# flyback.net
KiCad netlist of a schematic drawn in Altium Designer
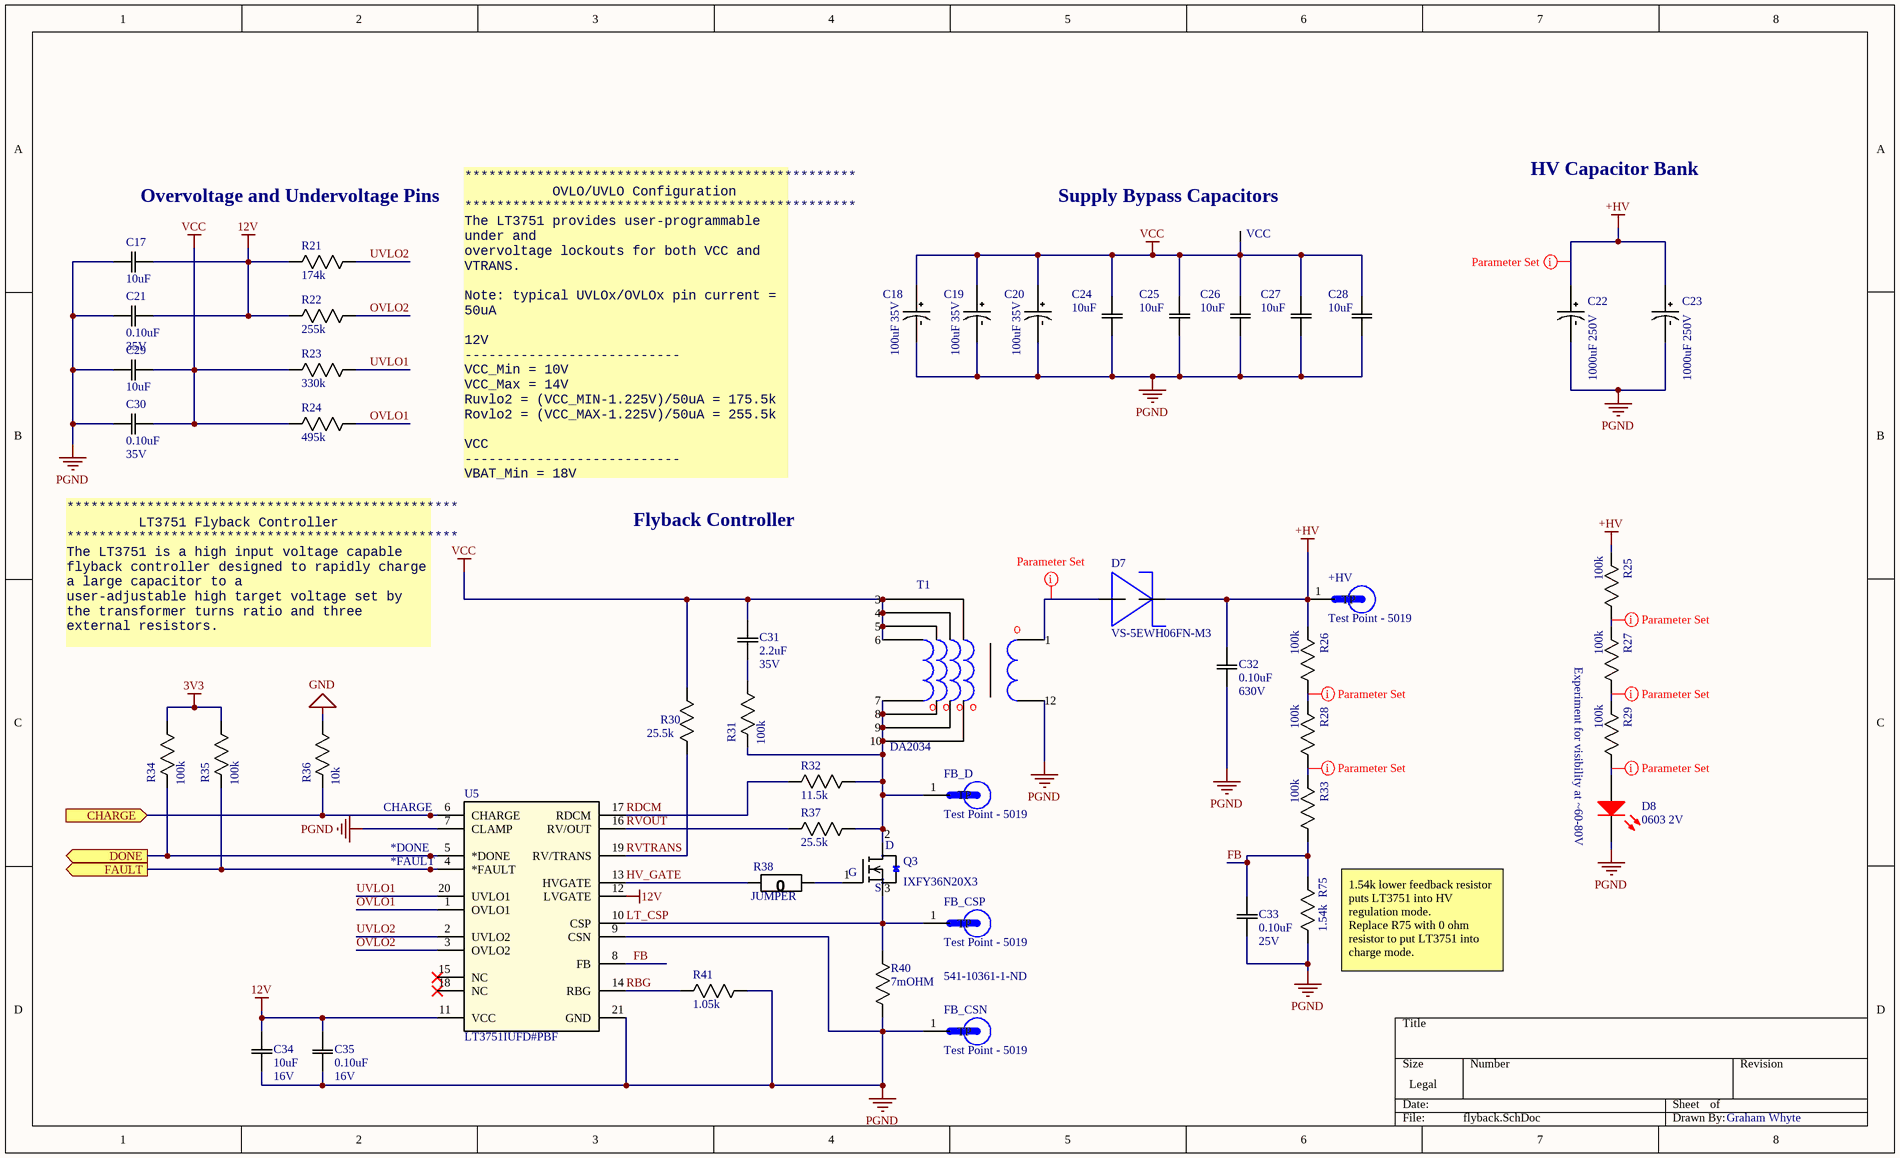
[diagram p0: flyback.SchDoc]

(export (version "E")
  (design (tool "Eeschema 10.0.6"))
  (components
    (comp (ref "*DONE")
      (value "Test Point (Via)")
      (footprint "TP")
      (libsource (lib "IC_Library") (part "Test Point (Via)"))
    )
    (comp (ref "*FAULT")
      (value "Test Point (Via)")
      (footprint "TP")
      (libsource (lib "IC_Library") (part "Test Point (Via)"))
    )
    (comp (ref "+HV")
      (value "Test Point - 5019")
      (footprint "TP380X203")
      (description "PC Test Point, Miniature Phosphor Bronze, Silver Plating Surface Mount Mounting Type")
      (fields (field (name "MP") "5019") (field (name "MF") "Keystone Electronics"))
      (libsource (lib "IC_Library") (part "Test Point - 5019"))
    )
    (comp (ref "C17")
      (value "10uF")
      (footprint "0805")
      (description "CAP CER 10UF 35V X7R 0805")
      (fields (field (name "TOLERANCE") "10%") (field (name "PART NUMBER") "CAP 10uF 35V"))
      (libsource (lib "capacitor_library") (part "CAP 10uF 35V"))
    )
    (comp (ref "C18")
      (value "100uF 35V")
      (footprint "CAP POL ALU 6.3x5.8")
      (description "CAP ALUM 100UF 35V SMD")
      (fields (field (name "TOLERANCE") "20%") (field (name "PART NUMBER") "CAP POL 100uF SMD"))
      (libsource (lib "capacitor_library") (part "CAP POL 100uF SMD"))
    )
    (comp (ref "C19")
      (value "100uF 35V")
      (footprint "CAP POL ALU 6.3x5.8")
      (description "CAP ALUM 100UF 35V SMD")
      (fields (field (name "TOLERANCE") "20%") (field (name "PART NUMBER") "CAP POL 100uF SMD"))
      (libsource (lib "capacitor_library") (part "CAP POL 100uF SMD"))
    )
    (comp (ref "C20")
      (value "100uF 35V")
      (footprint "CAP POL ALU 6.3x5.8")
      (description "CAP ALUM 100UF 35V SMD")
      (fields (field (name "TOLERANCE") "20%") (field (name "PART NUMBER") "CAP POL 100uF SMD"))
      (libsource (lib "capacitor_library") (part "CAP POL 100uF SMD"))
    )
    (comp (ref "C21")
      (value "0.10uF")
      (footprint "0805")
      (description "CAP CER 0.10UF 35V X7R 0805")
      (fields
        (field (name "TOLERANCE") "10%")
        (field (name "RATING") "35V")
        (field (name "PART NUMBER") "CAP 0.10uF 35V")
      )
      (libsource (lib "capacitor_library") (part "CAP 0.10uF 35V"))
    )
    (comp (ref "C22")
      (value "1000uF 250V")
      (footprint "RADIAL, CAN - THRU 25.4mm")
      (description "United Chemi-Con\r\nESMQ251VSN102MQ45S")
      (fields
        (field (name "MANUFACTURER") "United Chemi-Con")
        (field (name "MANUFACTURER PART NUMBER") "ESMQ251VSN102MQ45S")
      )
      (libsource (lib "capacitor_library") (part "CAP POL 1000uF"))
    )
    (comp (ref "C23")
      (value "1000uF 250V")
      (footprint "RADIAL, CAN - THRU 25.4mm")
      (description "United Chemi-Con\r\nESMQ251VSN102MQ45S")
      (fields
        (field (name "MANUFACTURER") "United Chemi-Con")
        (field (name "MANUFACTURER PART NUMBER") "ESMQ251VSN102MQ45S")
      )
      (libsource (lib "capacitor_library") (part "CAP POL 1000uF"))
    )
    (comp (ref "C24")
      (value "10uF")
      (footprint "0805")
      (description "CAP CER 10UF 35V X7R 0805")
      (fields (field (name "TOLERANCE") "10%") (field (name "PART NUMBER") "CAP 10uF 35V"))
      (libsource (lib "capacitor_library") (part "CAP 10uF 35V"))
    )
    (comp (ref "C25")
      (value "10uF")
      (footprint "0805")
      (description "CAP CER 10UF 35V X7R 0805")
      (fields (field (name "TOLERANCE") "10%") (field (name "PART NUMBER") "CAP 10uF 35V"))
      (libsource (lib "capacitor_library") (part "CAP 10uF 35V"))
    )
    (comp (ref "C26")
      (value "10uF")
      (footprint "0805")
      (description "CAP CER 10UF 35V X7R 0805")
      (fields (field (name "TOLERANCE") "10%") (field (name "PART NUMBER") "CAP 10uF 35V"))
      (libsource (lib "capacitor_library") (part "CAP 10uF 35V"))
    )
    (comp (ref "C27")
      (value "10uF")
      (footprint "0805")
      (description "CAP CER 10UF 35V X7R 0805")
      (fields (field (name "TOLERANCE") "10%") (field (name "PART NUMBER") "CAP 10uF 35V"))
      (libsource (lib "capacitor_library") (part "CAP 10uF 35V"))
    )
    (comp (ref "C28")
      (value "10uF")
      (footprint "0805")
      (description "CAP CER 10UF 35V X7R 0805")
      (fields (field (name "TOLERANCE") "10%") (field (name "PART NUMBER") "CAP 10uF 35V"))
      (libsource (lib "capacitor_library") (part "CAP 10uF 35V"))
    )
    (comp (ref "C29")
      (value "10uF")
      (footprint "0805")
      (description "CAP CER 10UF 35V X7R 0805")
      (fields (field (name "TOLERANCE") "10%") (field (name "PART NUMBER") "CAP 10uF 35V"))
      (libsource (lib "capacitor_library") (part "CAP 10uF 35V"))
    )
    (comp (ref "C30")
      (value "0.10uF")
      (footprint "0805")
      (description "CAP CER 0.10UF 35V X7R 0805")
      (fields
        (field (name "TOLERANCE") "10%")
        (field (name "RATING") "35V")
        (field (name "PART NUMBER") "CAP 0.10uF 35V")
      )
      (libsource (lib "capacitor_library") (part "CAP 0.10uF 35V"))
    )
    (comp (ref "C31")
      (value "2.2uF")
      (footprint "0603")
      (description "CAP CER 2.2UF 35V X7R 0603/0805")
      (fields
        (field (name "TOLERANCE") "10%")
        (field (name "RATING") "35V")
        (field (name "PART NUMBER") "CAP 2.2uF 35V")
      )
      (libsource (lib "capacitor_library") (part "CAP 2.2uF 35V"))
    )
    (comp (ref "C32")
      (value "0.10uF")
      (footprint "1210")
      (description "CAP CER 0.1uF 630V X7R 1210")
      (fields
        (field (name "TOLERANCE") "10%")
        (field (name "RATING") "630V")
        (field (name "PART NUMBER") "CAP 0.10uF 630V")
      )
      (libsource (lib "capacitor_library") (part "CAP 0.10uF 630V"))
    )
    (comp (ref "C33")
      (value "0.10uF")
      (footprint "0805")
      (description "CAP CER 0.10UF 25V X7R 0805")
      (fields
        (field (name "TOLERANCE") "10%")
        (field (name "RATING") "25V")
        (field (name "PART NUMBER") "CAP 0.10uF 25V")
      )
      (libsource (lib "capacitor_library") (part "CAP 0.10uF 25V"))
    )
    (comp (ref "C34")
      (value "10uF")
      (footprint "0603")
      (description "CAP CER 10UF 16V X5R 0603/0805")
      (fields
        (field (name "TOLERANCE") "10%")
        (field (name "RATING") "16V")
        (field (name "PART NUMBER") "CAP 10uF 16V")
      )
      (libsource (lib "capacitor_library") (part "CAP 10uF 16V"))
    )
    (comp (ref "C35")
      (value "0.10uF")
      (footprint "0603")
      (description "CAP CER 0.10UF 16V X5R 0603")
      (fields
        (field (name "TOLERANCE") "10%")
        (field (name "RATING") "16V")
        (field (name "PART NUMBER") "CAP 0.10uF 16V")
      )
      (libsource (lib "capacitor_library") (part "CAP 0.10uF 16V"))
    )
    (comp (ref "CHARGE")
      (value "Test Point (Via)")
      (footprint "TP")
      (libsource (lib "IC_Library") (part "Test Point (Via)"))
    )
    (comp (ref "D7")
      (value "VS-5EWH06FN-M3")
      (footprint "DPAK (TO-252)")
      (description "Diode Switching 600V 5A DPAK")
      (fields (field (name "MF") "Vishay Diodes"))
      (libsource (lib "Diode_Library") (part "VS-5EWH06FN-M3"))
    )
    (comp (ref "D8")
      (value "0603 2V")
      (footprint "0603 - LED2")
      (description "0603 red led alingap 631nm-639nm water clear 18-180mcd 130d")
      (fields (field (name "PART NUMBER") "LED RED SMD 0603"))
      (libsource (lib "Diode_Library") (part "LED RED SMD 0603"))
    )
    (comp (ref "FB_CSN")
      (value "Test Point - 5019")
      (footprint "TP380X203")
      (description "PC Test Point, Miniature Phosphor Bronze, Silver Plating Surface Mount Mounting Type")
      (fields (field (name "MP") "5019") (field (name "MF") "Keystone Electronics"))
      (libsource (lib "IC_Library") (part "Test Point - 5019"))
    )
    (comp (ref "FB_CSP")
      (value "Test Point - 5019")
      (footprint "TP380X203")
      (description "PC Test Point, Miniature Phosphor Bronze, Silver Plating Surface Mount Mounting Type")
      (fields (field (name "MP") "5019") (field (name "MF") "Keystone Electronics"))
      (libsource (lib "IC_Library") (part "Test Point - 5019"))
    )
    (comp (ref "FB_D")
      (value "Test Point - 5019")
      (footprint "TP380X203")
      (description "PC Test Point, Miniature Phosphor Bronze, Silver Plating Surface Mount Mounting Type")
      (fields (field (name "MP") "5019") (field (name "MF") "Keystone Electronics"))
      (libsource (lib "IC_Library") (part "Test Point - 5019"))
    )
    (comp (ref "Q3")
      (value "IXFY36N20X3")
      (footprint "DPAK (TO-252)")
      (description "N-Channel 200 V 36A (Tc) 176W (Tc) Surface Mount TO-252AA")
      (fields (field (name "PART NUMBER") "MOSFET N-CH IXFY36N20X3"))
      (libsource (lib "Transistor_Library") (part "MOSFET N-CH IXFY36N20X3"))
    )
    (comp (ref "R21")
      (value "174k")
      (footprint "0603")
      (description "RES SMD 174K OHM 1% 1/8W 0603")
      (fields
        (field (name "MANUFACTURER") "Yageo")
        (field (name "MANUFACTURER PART NUMBER") "RC0805FR-07174KL")
      )
      (libsource (lib "Resistor_Library") (part "RES 174k 1/8W"))
    )
    (comp (ref "R22")
      (value "255k")
      (footprint "0603")
      (description "RES 255k 1/8W - 1% 0603")
      (fields (field (name "PART NUMBER") "RES 255k 1/8W - 1%"))
      (libsource (lib "Resistor_Library") (part "RES 255k 1/8W - 1%"))
    )
    (comp (ref "R23")
      (value "330k")
      (footprint "0603")
      (description "RES SMD 274K OHM 1% 1/8W 0603")
      (fields (field (name "PART NUMBER") "RES 330k 1/8W - 1%"))
      (libsource (lib "Resistor_Library") (part "RES 330k 1/8W - 1%"))
    )
    (comp (ref "R24")
      (value "495k")
      (footprint "0603")
      (description "RES SMD 495K OHM 1% 1/8W 0603")
      (fields
        (field (name "MANUFACTURER") "Yageo")
        (field (name "MANUFACTURER PART NUMBER") "RC0805FR-07499KL")
      )
      (libsource (lib "Resistor_Library") (part "RES 495k 1/8W"))
    )
    (comp (ref "R25")
      (value "100k")
      (footprint "0603")
      (description "RES SMD 100K OHM 5% 1/8W 0603")
      (fields (field (name "TOLERANCE") "5%") (field (name "PART NUMBER") "RES 100k 1/8W - 5%"))
      (libsource (lib "") (part "RES 100k 1/8W 5%_1"))
    )
    (comp (ref "R26")
      (value "100k")
      (footprint "0603")
      (description "RES SMD 100K OHM 1% 1/8W 0603")
      (fields (field (name "TOLERANCE") "1%") (field (name "PART NUMBER") "RES 100k 1/8W - 1%"))
      (libsource (lib "") (part "RES 100k 1/8W 1%_1"))
    )
    (comp (ref "R27")
      (value "100k")
      (footprint "0603")
      (description "RES SMD 100K OHM 5% 1/8W 0603")
      (fields (field (name "TOLERANCE") "5%") (field (name "PART NUMBER") "RES 100k 1/8W - 5%"))
      (libsource (lib "Resistor_Library") (part "RES 100k 1/8W 5%"))
    )
    (comp (ref "R28")
      (value "100k")
      (footprint "0603")
      (description "RES SMD 100K OHM 1% 1/8W 0603")
      (fields (field (name "TOLERANCE") "1%") (field (name "PART NUMBER") "RES 100k 1/8W - 1%"))
      (libsource (lib "Resistor_Library") (part "RES 100k 1/8W 1%"))
    )
    (comp (ref "R29")
      (value "100k")
      (footprint "0603")
      (description "RES SMD 100K OHM 5% 1/8W 0603")
      (fields (field (name "TOLERANCE") "5%") (field (name "PART NUMBER") "RES 100k 1/8W - 5%"))
      (libsource (lib "Resistor_Library") (part "RES 100k 1/8W 5%"))
    )
    (comp (ref "R30")
      (value "25.5k")
      (footprint "0603")
      (description "RES SMD 25.5K OHM 0.1% 1/8W 0603")
      (fields
        (field (name "MANUFACTURER") "Panasonic")
        (field (name "MANUFACTURER PART NUMBER") "ERA-6AEB2552V")
      )
      (libsource (lib "Resistor_Library") (part "RES 25.5k 1/8W"))
    )
    (comp (ref "R31")
      (value "100k")
      (footprint "0603")
      (description "RES SMD 100K OHM 1% 1/8W 0603")
      (fields (field (name "TOLERANCE") "1%") (field (name "PART NUMBER") "RES 100k 1/8W - 1%"))
      (libsource (lib "") (part "RES 100k 1/8W 1%_1"))
    )
    (comp (ref "R32")
      (value "11.5k")
      (footprint "0603")
      (description "RES SMD 11.5K OHM 0.1% 1/8W 0603 Thin Film")
      (fields
        (field (name "MANUFACTURER") "Panasonic")
        (field (name "MANUFACTURER PART NUMBER") "ERA-6AEB1152V")
      )
      (libsource (lib "Resistor_Library") (part "RES 11.5k 1/8W"))
    )
    (comp (ref "R33")
      (value "100k")
      (footprint "0603")
      (description "RES SMD 100K OHM 1% 1/8W 0603")
      (fields (field (name "TOLERANCE") "1%") (field (name "PART NUMBER") "RES 100k 1/8W - 1%"))
      (libsource (lib "Resistor_Library") (part "RES 100k 1/8W 1%"))
    )
    (comp (ref "R34")
      (value "100k")
      (footprint "0603")
      (description "RES SMD 100K OHM 5% 1/8W 0603")
      (fields (field (name "TOLERANCE") "5%") (field (name "PART NUMBER") "RES 100k 1/8W - 5%"))
      (libsource (lib "Resistor_Library") (part "RES 100k 1/8W 5%"))
    )
    (comp (ref "R35")
      (value "100k")
      (footprint "0603")
      (description "RES SMD 100K OHM 5% 1/8W 0603")
      (fields (field (name "TOLERANCE") "5%") (field (name "PART NUMBER") "RES 100k 1/8W - 5%"))
      (libsource (lib "Resistor_Library") (part "RES 100k 1/8W 5%"))
    )
    (comp (ref "R36")
      (value "10k")
      (footprint "0603")
      (description "RES SMD 10K OHM 5% 1/8W 0603")
      (fields (field (name "TOLERANCE") "5%") (field (name "PART NUMBER") "RES 10k 1/8W - 5%"))
      (libsource (lib "Resistor_Library") (part "RES 10k 1/8W 5%"))
    )
    (comp (ref "R37")
      (value "25.5k")
      (footprint "0603")
      (description "RES SMD 25.5K OHM 0.1% 1/8W 0603")
      (fields
        (field (name "MANUFACTURER") "Panasonic")
        (field (name "MANUFACTURER PART NUMBER") "ERA-6AEB2552V")
      )
      (libsource (lib "Resistor_Library") (part "RES 25.5k 1/8W"))
    )
    (comp (ref "R38")
      (value "JUMPER")
      (footprint "0603")
      (description "RES SMD 0 OHM JUMPER GENERIC 0603")
      (fields (field (name "PART NUMBER") "RES 0 JUMPER"))
      (libsource (lib "Resistor_Library") (part "RES 0 JUMPER"))
    )
    (comp (ref "R40")
      (value "7mOHM")
      (footprint "2512")
      (description "RES SMD 7m OHM 1% 3W 2512")
      (fields
        (field (name "TOLERANCE") "1%")
        (field (name "MFG") "VISHAY")
        (field (name "SUPPLIER PART NUMBER 1") "541-10361-1-ND")
      )
      (libsource (lib "Resistor_Library") (part "RES 7m 3W"))
    )
    (comp (ref "R41")
      (value "1.05k")
      (footprint "0603")
      (description "RES SMD 1.05K OHM 0.1% 1/8W 0603")
      (fields (field (name "TOLERANCE") "0.1%") (field (name "PART NUMBER") "RES 1.05k 1/8W"))
      (libsource (lib "Resistor_Library") (part "RES 1.05k 1/8W"))
    )
    (comp (ref "R75")
      (value "1.54k")
      (footprint "0603")
      (description "RES SMD 1.54k OHM 1% 1/8W 0603")
      (fields (field (name "TOLERANCE") "1%") (field (name "PART NUMBER") "RES 1.54k 1_8W - 1%"))
      (libsource (lib "Resistor_Library") (part "RES 1.54k 1/8W - 1%"))
    )
    (comp (ref "T1")
      (value "DA2034")
      (footprint "DA2034")
      (description "Audio Transformers / Signal Transformers DA2032 Cap Chrgr For Linear LT3750/51")
      (libsource (lib "IC_Library") (part "DA2034"))
    )
    (comp (ref "U5")
      (value "LT3751IUFD#PBF")
      (footprint "QFN-20_UFD_LIT-M")
      (description "IC CTRLR CAP CHRGR 4.75V 20-QFN")
      (fields
        (field (name "MANUFACTURER_PART_NUMBER") "lt3751iufd#pbf")
        (field (name "COPYRIGHT") "Copyright (C) 2021 Ultra Librarian. All rights reserved.")
      )
      (libsource (lib "IC_Library") (part "LT3751IUFD#PBF"))
    )
    (comp (ref "VCC")
      (value "Test Point (Via)")
      (footprint "TP")
      (libsource (lib "IC_Library") (part "Test Point (Via)"))
    )
  )
  (nets
    (net (code "1") (name "+HV") (class "Default")
      (node (ref "+HV") (pin "1") (pinfunction "TP_1") (pintype "passive"))
      (node (ref "C22") (pin "POS") (pinfunction "POS_POS") (pintype "passive"))
      (node (ref "C23") (pin "POS") (pinfunction "POS_POS") (pintype "passive"))
      (node (ref "C32") (pin "1") (pinfunction "C1_1") (pintype "passive"))
      (node (ref "D7") (pin "OUT") (pinfunction "OUT_OUT") (pintype "passive"))
      (node (ref "R25") (pin "2") (pinfunction "R2_2") (pintype "passive"))
      (node (ref "R26") (pin "2") (pinfunction "R2_2") (pintype "passive"))
    )
    (net (code "3") (name "/CHARGE") (class "Default")
      (node (ref "CHARGE") (pin "1") (pinfunction "1_1") (pintype "passive"))
      (node (ref "R36") (pin "2") (pinfunction "R2_2") (pintype "passive"))
      (node (ref "U5") (pin "6") (pinfunction "CHARGE_6") (pintype "passive"))
    )
    (net (code "4") (name "/DONE") (class "Default")
      (node (ref "*DONE") (pin "1") (pinfunction "1_1") (pintype "passive"))
      (node (ref "R34") (pin "2") (pinfunction "R2_2") (pintype "passive"))
      (node (ref "U5") (pin "5") (pinfunction "*DONE_5") (pintype "passive"))
    )
    (net (code "5") (name "/FAULT") (class "Default")
      (node (ref "*FAULT") (pin "1") (pinfunction "1_1") (pintype "passive"))
      (node (ref "R35") (pin "2") (pinfunction "R2_2") (pintype "passive"))
      (node (ref "U5") (pin "4") (pinfunction "*FAULT_4") (pintype "passive"))
    )
    (net (code "6") (name "/FB") (class "Default")
      (node (ref "C33") (pin "1") (pinfunction "C1_1") (pintype "passive"))
      (node (ref "R33") (pin "1") (pinfunction "R1_1") (pintype "passive"))
      (node (ref "R75") (pin "2") (pinfunction "R2_2") (pintype "passive"))
      (node (ref "U5") (pin "8") (pinfunction "FB_8") (pintype "passive"))
    )
    (net (code "7") (name "/HV_GATE") (class "Default")
      (node (ref "R38") (pin "2") (pinfunction "R2_2") (pintype "passive"))
      (node (ref "U5") (pin "13") (pinfunction "HVGATE_13") (pintype "passive"))
    )
    (net (code "8") (name "/LT_CSP") (class "Default")
      (node (ref "FB_CSP") (pin "1") (pinfunction "TP_1") (pintype "passive"))
      (node (ref "Q3") (pin "3") (pinfunction "S_3") (pintype "passive"))
      (node (ref "R40") (pin "2") (pinfunction "R2_2") (pintype "passive"))
      (node (ref "U5") (pin "10") (pinfunction "CSP_10") (pintype "passive"))
    )
    (net (code "9") (name "/OVLO1") (class "Default")
      (node (ref "R24") (pin "1") (pinfunction "R1_1") (pintype "passive"))
      (node (ref "U5") (pin "1") (pinfunction "OVLO1_1") (pintype "passive"))
    )
    (net (code "10") (name "/OVLO2") (class "Default")
      (node (ref "R22") (pin "1") (pinfunction "R1_1") (pintype "passive"))
      (node (ref "U5") (pin "3") (pinfunction "OVLO2_3") (pintype "passive"))
    )
    (net (code "11") (name "/RBG") (class "Default")
      (node (ref "R41") (pin "2") (pinfunction "R2_2") (pintype "passive"))
      (node (ref "U5") (pin "14") (pinfunction "RBG_14") (pintype "passive"))
    )
    (net (code "12") (name "/RDCM") (class "Default")
      (node (ref "R32") (pin "2") (pinfunction "R2_2") (pintype "passive"))
      (node (ref "U5") (pin "17") (pinfunction "RDCM_17") (pintype "passive"))
    )
    (net (code "13") (name "/RVOUT") (class "Default")
      (node (ref "R37") (pin "2") (pinfunction "R2_2") (pintype "passive"))
      (node (ref "U5") (pin "16") (pinfunction "RV/OUT_16") (pintype "passive"))
    )
    (net (code "14") (name "/RVTRANS") (class "Default")
      (node (ref "R30") (pin "2") (pinfunction "R2_2") (pintype "passive"))
      (node (ref "U5") (pin "19") (pinfunction "RV/TRANS_19") (pintype "passive"))
    )
    (net (code "15") (name "/UVLO1") (class "Default")
      (node (ref "R23") (pin "1") (pinfunction "R1_1") (pintype "passive"))
      (node (ref "U5") (pin "20") (pinfunction "UVLO1_20") (pintype "passive"))
    )
    (net (code "16") (name "/UVLO2") (class "Default")
      (node (ref "R21") (pin "1") (pinfunction "R1_1") (pintype "passive"))
      (node (ref "U5") (pin "2") (pinfunction "UVLO2_2") (pintype "passive"))
    )
    (net (code "17") (name "3V3") (class "Default")
      (node (ref "R34") (pin "1") (pinfunction "R1_1") (pintype "passive"))
      (node (ref "R35") (pin "1") (pinfunction "R1_1") (pintype "passive"))
    )
    (net (code "18") (name "12V") (class "Default")
      (node (ref "C17") (pin "2") (pinfunction "C2_2") (pintype "passive"))
      (node (ref "C21") (pin "2") (pinfunction "C2_2") (pintype "passive"))
      (node (ref "C34") (pin "1") (pinfunction "C1_1") (pintype "passive"))
      (node (ref "C35") (pin "2") (pinfunction "C2_2") (pintype "passive"))
      (node (ref "R21") (pin "2") (pinfunction "R2_2") (pintype "passive"))
      (node (ref "R22") (pin "2") (pinfunction "R2_2") (pintype "passive"))
      (node (ref "U5") (pin "11") (pinfunction "VCC_11") (pintype "power_in"))
      (node (ref "U5") (pin "12") (pinfunction "LVGATE_12") (pintype "passive"))
    )
    (net (code "19") (name "GND") (class "Default")
      (node (ref "R36") (pin "1") (pinfunction "R1_1") (pintype "passive"))
    )
    (net (code "20") (name "Net-(C31-C1)") (class "Default")
      (node (ref "C31") (pin "1") (pinfunction "C1_1") (pintype "passive"))
      (node (ref "R31") (pin "1") (pinfunction "R1_1") (pintype "passive"))
    )
    (net (code "21") (name "Net-(D7-PadIN)") (class "Default")
      (node (ref "D7") (pin "IN") (pinfunction "IN_IN") (pintype "passive"))
      (node (ref "T1") (pin "1") (pinfunction "1_1") (pintype "passive"))
    )
    (net (code "22") (name "Net-(D8-A)") (class "Default")
      (node (ref "D8") (pin "1") (pinfunction "A_1") (pintype "passive"))
      (node (ref "R29") (pin "1") (pinfunction "R1_1") (pintype "passive"))
    )
    (net (code "23") (name "Net-(FB_D-TP)") (class "Default")
      (node (ref "FB_D") (pin "1") (pinfunction "TP_1") (pintype "passive"))
      (node (ref "Q3") (pin "2") (pinfunction "D_2") (pintype "passive"))
      (node (ref "R31") (pin "2") (pinfunction "R2_2") (pintype "passive"))
      (node (ref "R32") (pin "1") (pinfunction "R1_1") (pintype "passive"))
      (node (ref "R37") (pin "1") (pinfunction "R1_1") (pintype "passive"))
      (node (ref "T1") (pin "10") (pinfunction "10_10") (pintype "passive"))
      (node (ref "T1") (pin "7") (pinfunction "7_7") (pintype "passive"))
      (node (ref "T1") (pin "8") (pinfunction "8_8") (pintype "passive"))
      (node (ref "T1") (pin "9") (pinfunction "9_9") (pintype "passive"))
    )
    (net (code "24") (name "Net-(Q3-G)") (class "Default")
      (node (ref "Q3") (pin "1") (pinfunction "G_1") (pintype "passive"))
      (node (ref "R38") (pin "1") (pinfunction "R1_1") (pintype "passive"))
    )
    (net (code "25") (name "Net-(R25-R1)") (class "Default")
      (node (ref "R25") (pin "1") (pinfunction "R1_1") (pintype "passive"))
      (node (ref "R27") (pin "2") (pinfunction "R2_2") (pintype "passive"))
    )
    (net (code "26") (name "Net-(R26-R1)") (class "Default")
      (node (ref "R26") (pin "1") (pinfunction "R1_1") (pintype "passive"))
      (node (ref "R28") (pin "2") (pinfunction "R2_2") (pintype "passive"))
    )
    (net (code "27") (name "Net-(R27-R1)") (class "Default")
      (node (ref "R27") (pin "1") (pinfunction "R1_1") (pintype "passive"))
      (node (ref "R29") (pin "2") (pinfunction "R2_2") (pintype "passive"))
    )
    (net (code "28") (name "Net-(R28-R1)") (class "Default")
      (node (ref "R28") (pin "1") (pinfunction "R1_1") (pintype "passive"))
      (node (ref "R33") (pin "2") (pinfunction "R2_2") (pintype "passive"))
    )
    (net (code "29") (name "PGND") (class "Default")
      (node (ref "C17") (pin "1") (pinfunction "C1_1") (pintype "passive"))
      (node (ref "C18") (pin "NEG") (pinfunction "NEG_NEG") (pintype "passive"))
      (node (ref "C19") (pin "NEG") (pinfunction "NEG_NEG") (pintype "passive"))
      (node (ref "C20") (pin "NEG") (pinfunction "NEG_NEG") (pintype "passive"))
      (node (ref "C21") (pin "1") (pinfunction "C1_1") (pintype "passive"))
      (node (ref "C22") (pin "NEG") (pinfunction "NEG_NEG") (pintype "passive"))
      (node (ref "C23") (pin "NEG") (pinfunction "NEG_NEG") (pintype "passive"))
      (node (ref "C24") (pin "1") (pinfunction "C1_1") (pintype "passive"))
      (node (ref "C25") (pin "1") (pinfunction "C1_1") (pintype "passive"))
      (node (ref "C26") (pin "1") (pinfunction "C1_1") (pintype "passive"))
      (node (ref "C27") (pin "1") (pinfunction "C1_1") (pintype "passive"))
      (node (ref "C28") (pin "1") (pinfunction "C1_1") (pintype "passive"))
      (node (ref "C29") (pin "1") (pinfunction "C1_1") (pintype "passive"))
      (node (ref "C30") (pin "1") (pinfunction "C1_1") (pintype "passive"))
      (node (ref "C32") (pin "2") (pinfunction "C2_2") (pintype "passive"))
      (node (ref "C33") (pin "2") (pinfunction "C2_2") (pintype "passive"))
      (node (ref "C34") (pin "2") (pinfunction "C2_2") (pintype "passive"))
      (node (ref "C35") (pin "1") (pinfunction "C1_1") (pintype "passive"))
      (node (ref "D8") (pin "2") (pinfunction "K_2") (pintype "passive"))
      (node (ref "FB_CSN") (pin "1") (pinfunction "TP_1") (pintype "passive"))
      (node (ref "R40") (pin "1") (pinfunction "R1_1") (pintype "passive"))
      (node (ref "R41") (pin "1") (pinfunction "R1_1") (pintype "passive"))
      (node (ref "R75") (pin "1") (pinfunction "R1_1") (pintype "passive"))
      (node (ref "T1") (pin "12") (pinfunction "12_12") (pintype "passive"))
      (node (ref "U5") (pin "21") (pinfunction "GND_21") (pintype "passive"))
      (node (ref "U5") (pin "7") (pinfunction "CLAMP_7") (pintype "passive"))
      (node (ref "U5") (pin "9") (pinfunction "CSN_9") (pintype "passive"))
    )
    (net (code "30") (name "VCC") (class "Default")
      (node (ref "C18") (pin "POS") (pinfunction "POS_POS") (pintype "passive"))
      (node (ref "C19") (pin "POS") (pinfunction "POS_POS") (pintype "passive"))
      (node (ref "C20") (pin "POS") (pinfunction "POS_POS") (pintype "passive"))
      (node (ref "C24") (pin "2") (pinfunction "C2_2") (pintype "passive"))
      (node (ref "C25") (pin "2") (pinfunction "C2_2") (pintype "passive"))
      (node (ref "C26") (pin "2") (pinfunction "C2_2") (pintype "passive"))
      (node (ref "C27") (pin "2") (pinfunction "C2_2") (pintype "passive"))
      (node (ref "C28") (pin "2") (pinfunction "C2_2") (pintype "passive"))
      (node (ref "C29") (pin "2") (pinfunction "C2_2") (pintype "passive"))
      (node (ref "C30") (pin "2") (pinfunction "C2_2") (pintype "passive"))
      (node (ref "C31") (pin "2") (pinfunction "C2_2") (pintype "passive"))
      (node (ref "R23") (pin "2") (pinfunction "R2_2") (pintype "passive"))
      (node (ref "R24") (pin "2") (pinfunction "R2_2") (pintype "passive"))
      (node (ref "R30") (pin "1") (pinfunction "R1_1") (pintype "passive"))
      (node (ref "T1") (pin "3") (pinfunction "3_3") (pintype "passive"))
      (node (ref "T1") (pin "4") (pinfunction "4_4") (pintype "passive"))
      (node (ref "T1") (pin "5") (pinfunction "5_5") (pintype "passive"))
      (node (ref "T1") (pin "6") (pinfunction "6_6") (pintype "passive"))
      (node (ref "VCC") (pin "1") (pinfunction "1_1") (pintype "passive"))
    )
    (net (code "31") (name "unconnected-(U5-NC-Pad15)") (class "Default")
      (node (ref "U5") (pin "15") (pinfunction "NC_15") (pintype "passive+no_connect"))
    )
    (net (code "32") (name "unconnected-(U5-NC-Pad18)") (class "Default")
      (node (ref "U5") (pin "18") (pinfunction "NC_18") (pintype "passive+no_connect"))
    )
  )
)
